# mechanics.net
KiCad netlist of a schematic drawn in Altium Designer
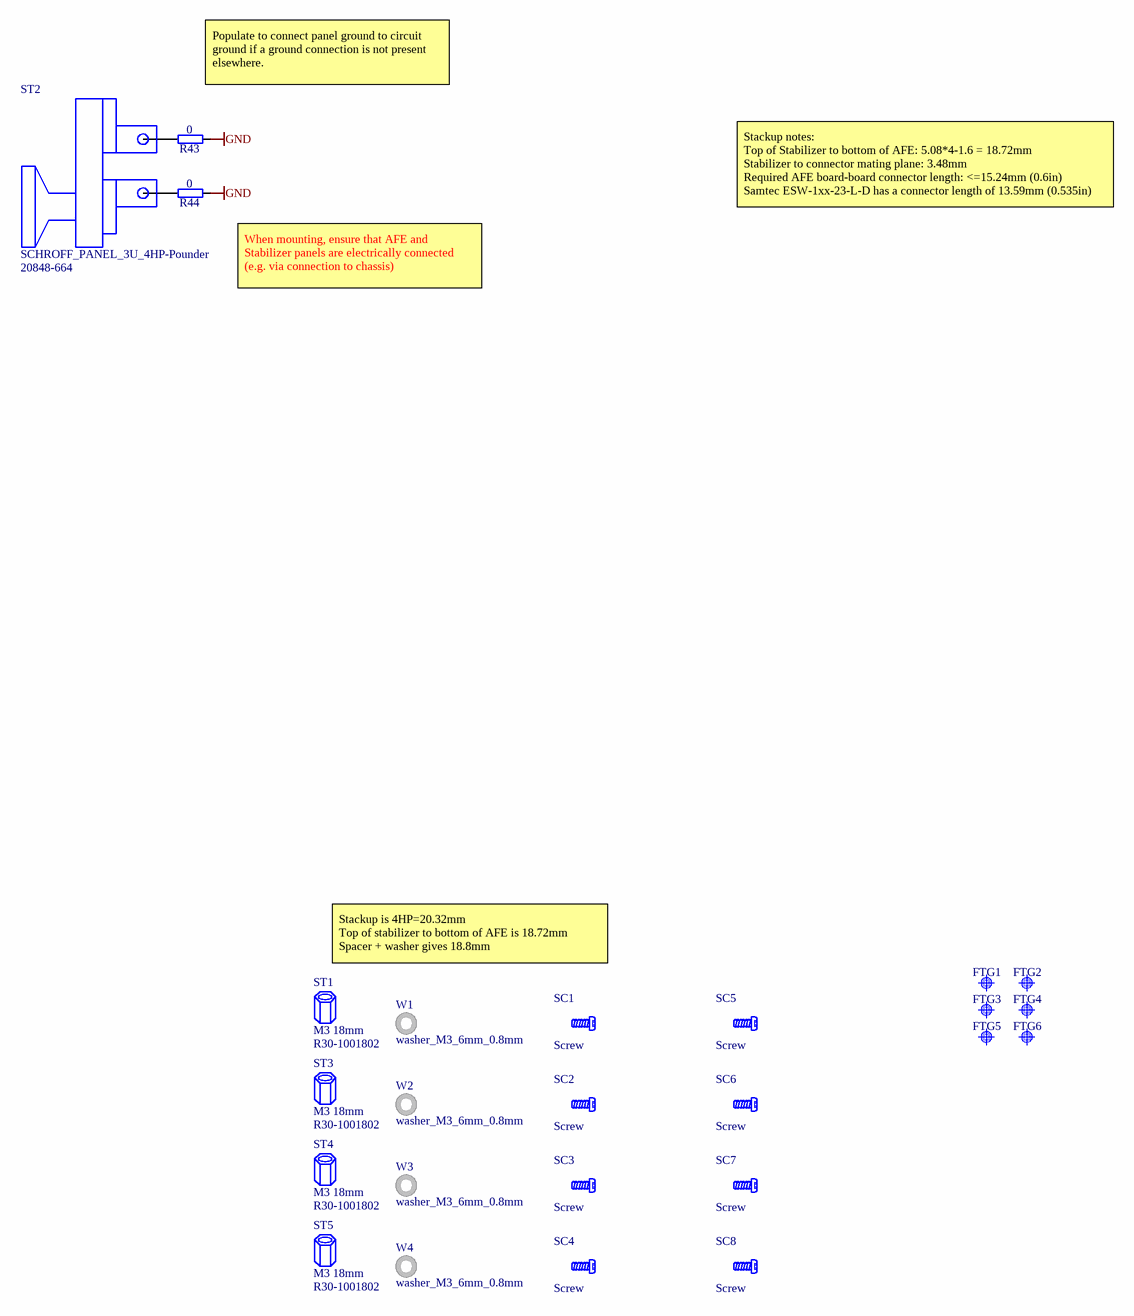
[diagram p0: mechanics.SchDoc]

(export (version "E")
  (design (tool "Eeschema 10.0.6"))
  (components
    (comp (ref "FTG1")
      (value "Use only in PCB")
      (footprint "FIDUCIAL_TOP_C100-200")
      (description "Fiducial Target")
      (fields (field (name "PART NUMBER") "FIDUCIAL_TARGET_C100-200") (field (name "AUTHOR") "CERN DEM JLC"))
      (libsource (lib "Eletro-mechanical") (part "Fiducial Target"))
    )
    (comp (ref "FTG2")
      (value "Use only in PCB")
      (footprint "FIDUCIAL_TOP_C100-200")
      (description "Fiducial Target")
      (fields (field (name "PART NUMBER") "FIDUCIAL_TARGET_C100-200") (field (name "AUTHOR") "CERN DEM JLC"))
      (libsource (lib "Eletro-mechanical") (part "Fiducial Target"))
    )
    (comp (ref "FTG3")
      (value "Use only in PCB")
      (footprint "FIDUCIAL_TOP_C100-200")
      (description "Fiducial Target")
      (fields (field (name "PART NUMBER") "FIDUCIAL_TARGET_C100-200") (field (name "AUTHOR") "CERN DEM JLC"))
      (libsource (lib "Eletro-mechanical") (part "Fiducial Target"))
    )
    (comp (ref "FTG4")
      (value "Use only in PCB")
      (footprint "FIDUCIAL_TOP_C100-200")
      (description "Fiducial Target")
      (fields (field (name "PART NUMBER") "FIDUCIAL_TARGET_C100-200") (field (name "AUTHOR") "CERN DEM JLC"))
      (libsource (lib "Eletro-mechanical") (part "Fiducial Target"))
    )
    (comp (ref "FTG5")
      (value "Use only in PCB")
      (footprint "FIDUCIAL_TOP_C100-200")
      (description "Fiducial Target")
      (fields (field (name "PART NUMBER") "FIDUCIAL_TARGET_C100-200") (field (name "AUTHOR") "CERN DEM JLC"))
      (libsource (lib "Eletro-mechanical") (part "Fiducial Target"))
    )
    (comp (ref "FTG6")
      (value "Use only in PCB")
      (footprint "FIDUCIAL_TOP_C100-200")
      (description "Fiducial Target")
      (fields (field (name "PART NUMBER") "FIDUCIAL_TARGET_C100-200") (field (name "AUTHOR") "CERN DEM JLC"))
      (libsource (lib "Eletro-mechanical") (part "Fiducial Target"))
    )
    (comp (ref "R43")
      (value "0")
      (footprint "RESC1608X55N")
      (description "Resistor")
      (fields
        (field (name "PART NUMBER") "R0603_0R_JUMPER")
        (field (name "MANUFACTURER") "GENERIC")
        (field (name "AUTHOR") "CERN DEM JLC")
      )
      (libsource (lib "Resistors") (part "Resistor"))
    )
    (comp (ref "R44")
      (value "0")
      (footprint "RESC1608X55N")
      (description "Resistor")
      (fields
        (field (name "PART NUMBER") "R0603_0R_JUMPER")
        (field (name "MANUFACTURER") "GENERIC")
        (field (name "AUTHOR") "CERN DEM JLC")
      )
      (libsource (lib "Resistors") (part "Resistor"))
    )
    (comp (ref "SC1")
      (value "Screw")
      (footprint "BOSSARD_BN5687-3061605_v")
      (fields
        (field (name "MANUFACTURER") "BOSSARD")
        (field (name "MANUFACTURER PART NUMBER") "BN5687 Art.3061605")
        (field (name "PART NUMBER") "BOSSARD_BN5687-3061605_v")
        (field (name "AUTHOR") "CERN DEM JLC")
      )
      (libsource (lib "Eletro-mechanical") (part "Screw"))
    )
    (comp (ref "SC2")
      (value "Screw")
      (footprint "BOSSARD_BN5687-3061605_v")
      (fields
        (field (name "MANUFACTURER") "BOSSARD")
        (field (name "MANUFACTURER PART NUMBER") "BN5687 Art.3061605")
        (field (name "PART NUMBER") "BOSSARD_BN5687-3061605_v")
        (field (name "AUTHOR") "CERN DEM JLC")
      )
      (libsource (lib "Eletro-mechanical") (part "Screw"))
    )
    (comp (ref "SC3")
      (value "Screw")
      (footprint "BOSSARD_BN5687-3061605_v")
      (fields
        (field (name "MANUFACTURER") "BOSSARD")
        (field (name "MANUFACTURER PART NUMBER") "BN5687 Art.3061605")
        (field (name "PART NUMBER") "BOSSARD_BN5687-3061605_v")
        (field (name "AUTHOR") "CERN DEM JLC")
      )
      (libsource (lib "Eletro-mechanical") (part "Screw"))
    )
    (comp (ref "SC4")
      (value "Screw")
      (footprint "BOSSARD_BN5687-3061605_v")
      (fields
        (field (name "MANUFACTURER") "BOSSARD")
        (field (name "MANUFACTURER PART NUMBER") "BN5687 Art.3061605")
        (field (name "PART NUMBER") "BOSSARD_BN5687-3061605_v")
        (field (name "AUTHOR") "CERN DEM JLC")
      )
      (libsource (lib "Eletro-mechanical") (part "Screw"))
    )
    (comp (ref "SC5")
      (value "Screw")
      (footprint "BOSSARD_BN5687-3061605_v")
      (fields
        (field (name "MANUFACTURER") "BOSSARD")
        (field (name "MANUFACTURER PART NUMBER") "BN5687 Art.3061605")
        (field (name "PART NUMBER") "BOSSARD_BN5687-3061605_v")
        (field (name "AUTHOR") "CERN DEM JLC")
      )
      (libsource (lib "Eletro-mechanical") (part "Screw"))
    )
    (comp (ref "SC6")
      (value "Screw")
      (footprint "BOSSARD_BN5687-3061605_v")
      (fields
        (field (name "MANUFACTURER") "BOSSARD")
        (field (name "MANUFACTURER PART NUMBER") "BN5687 Art.3061605")
        (field (name "PART NUMBER") "BOSSARD_BN5687-3061605_v")
        (field (name "AUTHOR") "CERN DEM JLC")
      )
      (libsource (lib "Eletro-mechanical") (part "Screw"))
    )
    (comp (ref "SC7")
      (value "Screw")
      (footprint "BOSSARD_BN5687-3061605_v")
      (fields
        (field (name "MANUFACTURER") "BOSSARD")
        (field (name "MANUFACTURER PART NUMBER") "BN5687 Art.3061605")
        (field (name "PART NUMBER") "BOSSARD_BN5687-3061605_v")
        (field (name "AUTHOR") "CERN DEM JLC")
      )
      (libsource (lib "Eletro-mechanical") (part "Screw"))
    )
    (comp (ref "SC8")
      (value "Screw")
      (footprint "BOSSARD_BN5687-3061605_v")
      (fields
        (field (name "MANUFACTURER") "BOSSARD")
        (field (name "MANUFACTURER PART NUMBER") "BN5687 Art.3061605")
        (field (name "PART NUMBER") "BOSSARD_BN5687-3061605_v")
        (field (name "AUTHOR") "CERN DEM JLC")
      )
      (libsource (lib "Eletro-mechanical") (part "Screw"))
    )
    (comp (ref "ST1")
      (value "M3 18mm")
      (footprint "mechanical:R30-1001802")
      (description "M3.0x18 standoff")
      (fields (field (name "MANUFACTURER") "Harwin") (field (name "MANUFACTURER PART NUMBER") "R30-1001802"))
      (libsource (lib "mechanical") (part "STANDOFF_HARWIN_R30_1001802"))
    )
    (comp (ref "ST2")
      (value "SCHROFF_PANEL_3U_4HP-Pounder")
      (footprint "SCHROFF_PANEL_3HP_4U - Pounder")
      (description "Schroff 3HP 4U EUROCARD Panel")
      (fields
        (field (name "MANUFACTURER") "Schroff")
        (field (name "MANUFACTURER PART NUMBER") "20818-017")
        (field (name "MANUFACTURER PART NUMBER 2") "20848-664")
      )
      (libsource (lib "Mechanical") (part "SCHROFF_PANEL_3U_4HP_Pounder"))
    )
    (comp (ref "ST3")
      (value "M3 18mm")
      (footprint "mechanical:R30-1001802")
      (description "M3.0x18 standoff")
      (fields (field (name "MANUFACTURER") "Harwin") (field (name "MANUFACTURER PART NUMBER") "R30-1001802"))
      (libsource (lib "mechanical") (part "STANDOFF_HARWIN_R30_1001802"))
    )
    (comp (ref "ST4")
      (value "M3 18mm")
      (footprint "mechanical:R30-1001802")
      (description "M3.0x18 standoff")
      (fields (field (name "MANUFACTURER") "Harwin") (field (name "MANUFACTURER PART NUMBER") "R30-1001802"))
      (libsource (lib "mechanical") (part "STANDOFF_HARWIN_R30_1001802"))
    )
    (comp (ref "ST5")
      (value "M3 18mm")
      (footprint "mechanical:R30-1001802")
      (description "M3.0x18 standoff")
      (fields (field (name "MANUFACTURER") "Harwin") (field (name "MANUFACTURER PART NUMBER") "R30-1001802"))
      (libsource (lib "mechanical") (part "STANDOFF_HARWIN_R30_1001802"))
    )
    (comp (ref "W1")
      (value "washer_M3_6mm_0.8mm")
      (footprint "mechanical:washer_M3_6mm_0.8mm")
      (description "M3 Washer:\r\nID: 3.2mm\r\nOD: 6mm\r\nThickness 0.8mm")
      (fields
        (field (name "MANUFACTURER") "Accu Limited")
        (field (name "MANUFACTURER PART NUMBER") "HAFZ-M3-A4")
      )
      (libsource (lib "mechanical") (part "washer_M3_6mm_0.8mm"))
    )
    (comp (ref "W2")
      (value "washer_M3_6mm_0.8mm")
      (footprint "mechanical:washer_M3_6mm_0.8mm")
      (description "M3 Washer:\r\nID: 3.2mm\r\nOD: 6mm\r\nThickness 0.8mm")
      (fields
        (field (name "MANUFACTURER") "Accu Limited")
        (field (name "MANUFACTURER PART NUMBER") "HAFZ-M3-A4")
      )
      (libsource (lib "mechanical") (part "washer_M3_6mm_0.8mm"))
    )
    (comp (ref "W3")
      (value "washer_M3_6mm_0.8mm")
      (footprint "mechanical:washer_M3_6mm_0.8mm")
      (description "M3 Washer:\r\nID: 3.2mm\r\nOD: 6mm\r\nThickness 0.8mm")
      (fields
        (field (name "MANUFACTURER") "Accu Limited")
        (field (name "MANUFACTURER PART NUMBER") "HAFZ-M3-A4")
      )
      (libsource (lib "mechanical") (part "washer_M3_6mm_0.8mm"))
    )
    (comp (ref "W4")
      (value "washer_M3_6mm_0.8mm")
      (footprint "mechanical:washer_M3_6mm_0.8mm")
      (description "M3 Washer:\r\nID: 3.2mm\r\nOD: 6mm\r\nThickness 0.8mm")
      (fields
        (field (name "MANUFACTURER") "Accu Limited")
        (field (name "MANUFACTURER PART NUMBER") "HAFZ-M3-A4")
      )
      (libsource (lib "mechanical") (part "washer_M3_6mm_0.8mm"))
    )
  )
  (nets
    (net (code "1") (name "GND") (class "Default")
      (node (ref "R43") (pin "1") (pinfunction "1_1") (pintype "passive"))
      (node (ref "R44") (pin "1") (pinfunction "1_1") (pintype "passive"))
    )
    (net (code "2") (name "Net-(R43-Pad2)") (class "Default")
      (node (ref "R43") (pin "2") (pinfunction "2_2") (pintype "passive"))
      (node (ref "ST2") (pin "1") (pinfunction "1_1") (pintype "passive"))
    )
    (net (code "3") (name "Net-(R44-Pad2)") (class "Default")
      (node (ref "R44") (pin "2") (pinfunction "2_2") (pintype "passive"))
      (node (ref "ST2") (pin "0") (pinfunction "0_0") (pintype "passive"))
    )
  )
)
